# main.net
KiCad netlist of a schematic drawn in EAGLE
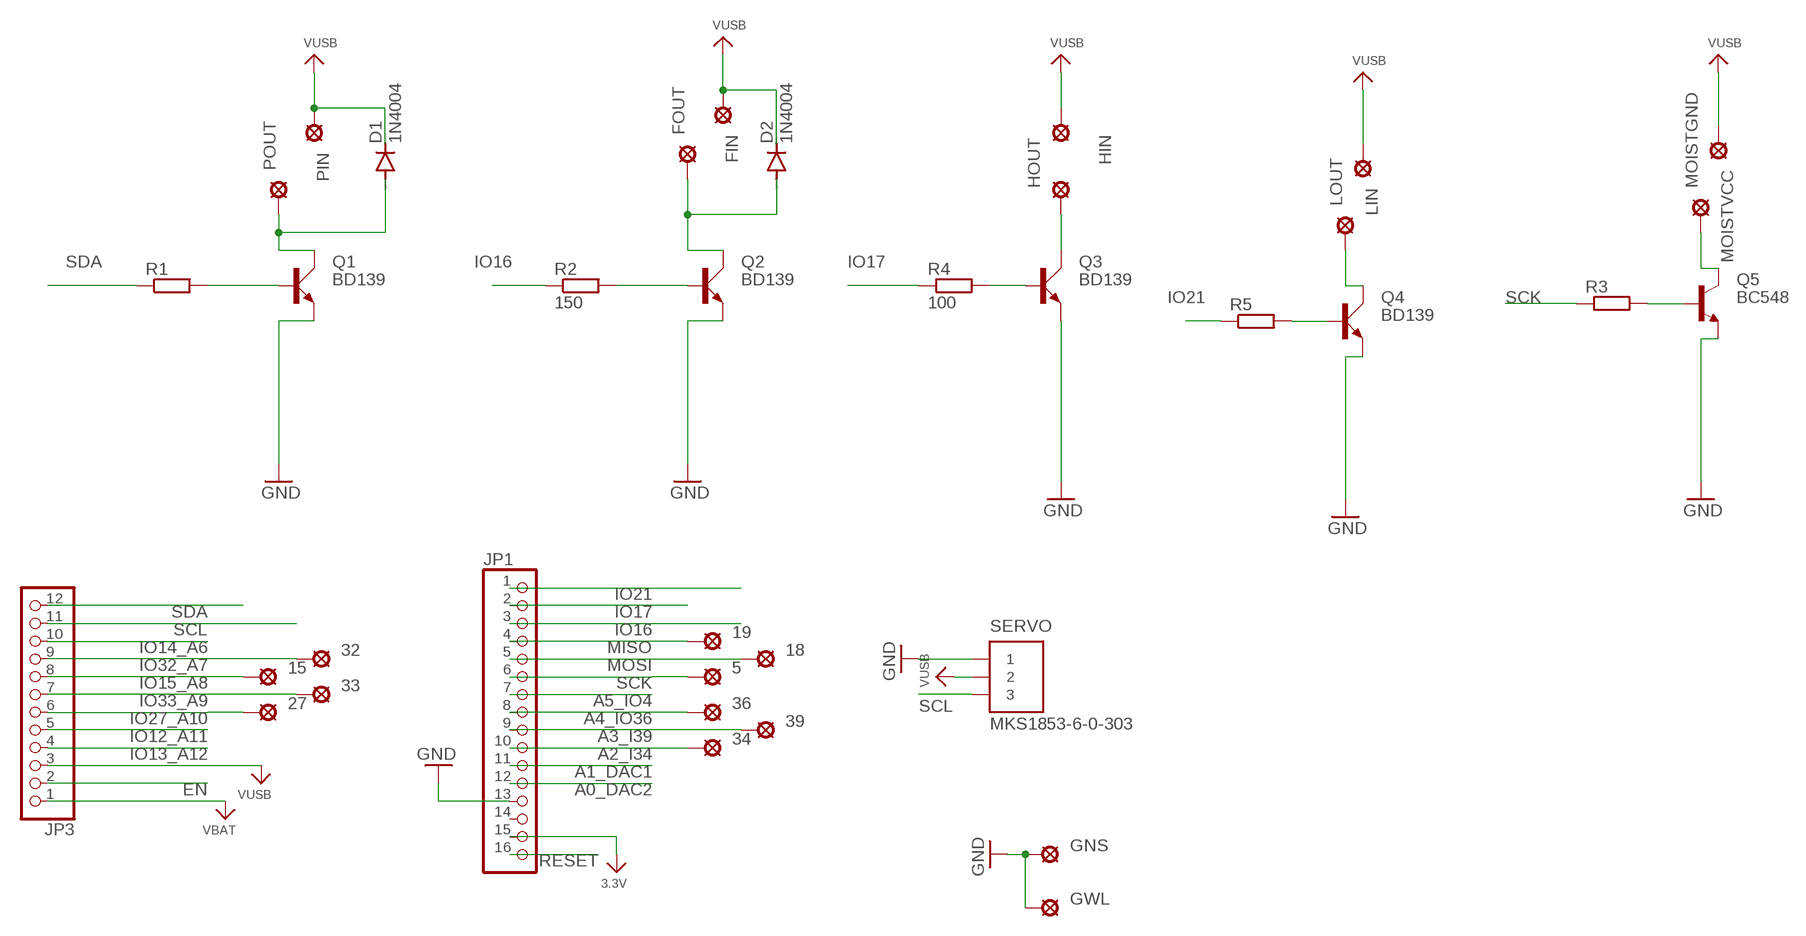
[diagram p0: schematic, sheet 1]

(export (version "E")
  (design (tool "Eeschema 10.0.6"))
  (components
    (comp (ref "5")
      (value "SE13")
      (footprint "eagle-import:SE13")
      (libsource (lib "eagle-import") (part "SE13"))
    )
    (comp (ref "15")
      (value "SE13")
      (footprint "eagle-import:SE13")
      (libsource (lib "eagle-import") (part "SE13"))
    )
    (comp (ref "18")
      (value "SE13")
      (footprint "eagle-import:SE13")
      (libsource (lib "eagle-import") (part "SE13"))
    )
    (comp (ref "19")
      (value "SE13")
      (footprint "eagle-import:SE13")
      (libsource (lib "eagle-import") (part "SE13"))
    )
    (comp (ref "27")
      (value "SE13")
      (footprint "eagle-import:SE13")
      (libsource (lib "eagle-import") (part "SE13"))
    )
    (comp (ref "32")
      (value "SE13")
      (footprint "eagle-import:SE13")
      (libsource (lib "eagle-import") (part "SE13"))
    )
    (comp (ref "33")
      (value "SE13")
      (footprint "eagle-import:SE13")
      (libsource (lib "eagle-import") (part "SE13"))
    )
    (comp (ref "34")
      (value "SE13")
      (footprint "eagle-import:SE13")
      (libsource (lib "eagle-import") (part "SE13"))
    )
    (comp (ref "36")
      (value "SE13")
      (footprint "eagle-import:SE13")
      (libsource (lib "eagle-import") (part "SE13"))
    )
    (comp (ref "39")
      (value "SE13")
      (footprint "eagle-import:SE13")
      (libsource (lib "eagle-import") (part "SE13"))
    )
    (comp (ref "D1")
      (value "1N4004")
      (footprint "eagle-import:DO41-10")
      (libsource (lib "eagle-import") (part "1N4004"))
    )
    (comp (ref "D2")
      (value "1N4004")
      (footprint "eagle-import:DO41-10")
      (libsource (lib "eagle-import") (part "1N4004"))
    )
    (comp (ref "FIN")
      (value "SE13")
      (footprint "eagle-import:SE13")
      (libsource (lib "eagle-import") (part "SE13"))
    )
    (comp (ref "FOUT")
      (value "SE13")
      (footprint "eagle-import:SE13")
      (libsource (lib "eagle-import") (part "SE13"))
    )
    (comp (ref "GNS")
      (value "SE13")
      (footprint "eagle-import:SE13")
      (libsource (lib "eagle-import") (part "SE13"))
    )
    (comp (ref "GWL")
      (value "SE13")
      (footprint "eagle-import:SE13")
      (libsource (lib "eagle-import") (part "SE13"))
    )
    (comp (ref "HIN")
      (value "SE13")
      (footprint "eagle-import:SE13")
      (libsource (lib "eagle-import") (part "SE13"))
    )
    (comp (ref "HOUT")
      (value "SE13")
      (footprint "eagle-import:SE13")
      (libsource (lib "eagle-import") (part "SE13"))
    )
    (comp (ref "JP1")
      (value "HEADER-1X16_MIN")
      (footprint "eagle-import:1X16_ROUND_MIN")
      (libsource (lib "eagle-import") (part "HEADER-1X16_MIN"))
    )
    (comp (ref "JP3")
      (value "HEADER-1X12_MIN")
      (footprint "eagle-import:1X12_ROUND_MIN")
      (libsource (lib "eagle-import") (part "HEADER-1X12_MIN"))
    )
    (comp (ref "LIN")
      (value "SE13")
      (footprint "eagle-import:SE13")
      (libsource (lib "eagle-import") (part "SE13"))
    )
    (comp (ref "LOUT")
      (value "SE13")
      (footprint "eagle-import:SE13")
      (libsource (lib "eagle-import") (part "SE13"))
    )
    (comp (ref "MOISTGND")
      (value "SE13")
      (footprint "eagle-import:SE13")
      (libsource (lib "eagle-import") (part "SE13"))
    )
    (comp (ref "MOISTVCC")
      (value "SE13")
      (footprint "eagle-import:SE13")
      (libsource (lib "eagle-import") (part "SE13"))
    )
    (comp (ref "PIN")
      (value "SE13")
      (footprint "eagle-import:SE13")
      (libsource (lib "eagle-import") (part "SE13"))
    )
    (comp (ref "POUT")
      (value "SE13")
      (footprint "eagle-import:SE13")
      (libsource (lib "eagle-import") (part "SE13"))
    )
    (comp (ref "Q1")
      (value "BD139")
      (footprint "eagle-import:TO126AV")
      (libsource (lib "eagle-import") (part "BD139"))
    )
    (comp (ref "Q2")
      (value "BD139")
      (footprint "eagle-import:TO126AV")
      (libsource (lib "eagle-import") (part "BD139"))
    )
    (comp (ref "Q3")
      (value "BD139")
      (footprint "eagle-import:TO126AV")
      (libsource (lib "eagle-import") (part "BD139"))
    )
    (comp (ref "Q4")
      (value "BD139")
      (footprint "eagle-import:TO126AV")
      (libsource (lib "eagle-import") (part "BD139"))
    )
    (comp (ref "Q5")
      (value "BC548")
      (footprint "eagle-import:TO92-EBC")
      (libsource (lib "eagle-import") (part "BC548"))
    )
    (comp (ref "R1")
      (value "R-EU_R0805")
      (footprint "eagle-import:R0805")
      (libsource (lib "eagle-import") (part "R-EU_R0805"))
    )
    (comp (ref "R2")
      (value "150")
      (footprint "eagle-import:R0805")
      (libsource (lib "eagle-import") (part "R-EU_R0805"))
    )
    (comp (ref "R3")
      (value "R-EU_R0805")
      (footprint "eagle-import:R0805")
      (libsource (lib "eagle-import") (part "R-EU_R0805"))
    )
    (comp (ref "R4")
      (value "100")
      (footprint "eagle-import:R0805")
      (libsource (lib "eagle-import") (part "R-EU_R0805"))
    )
    (comp (ref "R5")
      (value "R-EU_R0805")
      (footprint "eagle-import:R0805")
      (libsource (lib "eagle-import") (part "R-EU_R0805"))
    )
    (comp (ref "SERVO")
      (value "MKS1853-6-0-303")
      (footprint "eagle-import:MKS1853-6-0-303")
      (libsource (lib "eagle-import") (part "MKS1853-6-0-303"))
    )
  )
  (nets
    (net (code "1") (name "/A0_DAC2") (class "Default")
      (node (ref "JP1") (pin "12") (pinfunction "12_12") (pintype "passive"))
    )
    (net (code "2") (name "/A1_DAC1") (class "Default")
      (node (ref "JP1") (pin "11") (pinfunction "11_11") (pintype "passive"))
    )
    (net (code "3") (name "/A2_I34") (class "Default")
      (node (ref "34") (pin "MP") (pinfunction "MP_MP") (pintype "passive"))
      (node (ref "JP1") (pin "10") (pinfunction "10_10") (pintype "passive"))
    )
    (net (code "4") (name "/A3_I39") (class "Default")
      (node (ref "39") (pin "MP") (pinfunction "MP_MP") (pintype "passive"))
      (node (ref "JP1") (pin "9") (pinfunction "9_9") (pintype "passive"))
    )
    (net (code "5") (name "/A4_IO36") (class "Default")
      (node (ref "36") (pin "MP") (pinfunction "MP_MP") (pintype "passive"))
      (node (ref "JP1") (pin "8") (pinfunction "8_8") (pintype "passive"))
    )
    (net (code "6") (name "/A5_IO4") (class "Default")
      (node (ref "JP1") (pin "7") (pinfunction "7_7") (pintype "passive"))
    )
    (net (code "7") (name "/EN") (class "Default")
      (node (ref "JP3") (pin "2") (pinfunction "2_2") (pintype "passive"))
    )
    (net (code "8") (name "/IO12_A11") (class "Default")
      (node (ref "JP3") (pin "5") (pinfunction "5_5") (pintype "passive"))
    )
    (net (code "9") (name "/IO13_A12") (class "Default")
      (node (ref "JP3") (pin "4") (pinfunction "4_4") (pintype "passive"))
    )
    (net (code "10") (name "/IO14_A6") (class "Default")
      (node (ref "JP3") (pin "10") (pinfunction "10_10") (pintype "passive"))
    )
    (net (code "11") (name "/IO15_A8") (class "Default")
      (node (ref "15") (pin "MP") (pinfunction "MP_MP") (pintype "passive"))
      (node (ref "JP3") (pin "8") (pinfunction "8_8") (pintype "passive"))
    )
    (net (code "12") (name "/IO16") (class "Default")
      (node (ref "JP1") (pin "3") (pinfunction "3_3") (pintype "passive"))
      (node (ref "R2") (pin "1") (pinfunction "1_1") (pintype "passive"))
    )
    (net (code "13") (name "/IO17") (class "Default")
      (node (ref "JP1") (pin "2") (pinfunction "2_2") (pintype "passive"))
      (node (ref "R4") (pin "1") (pinfunction "1_1") (pintype "passive"))
    )
    (net (code "14") (name "/IO21") (class "Default")
      (node (ref "JP1") (pin "1") (pinfunction "1_1") (pintype "passive"))
      (node (ref "R5") (pin "1") (pinfunction "1_1") (pintype "passive"))
    )
    (net (code "15") (name "/IO27_A10") (class "Default")
      (node (ref "27") (pin "MP") (pinfunction "MP_MP") (pintype "passive"))
      (node (ref "JP3") (pin "6") (pinfunction "6_6") (pintype "passive"))
    )
    (net (code "16") (name "/IO32_A7") (class "Default")
      (node (ref "32") (pin "MP") (pinfunction "MP_MP") (pintype "passive"))
      (node (ref "JP3") (pin "9") (pinfunction "9_9") (pintype "passive"))
    )
    (net (code "17") (name "/IO33_A9") (class "Default")
      (node (ref "33") (pin "MP") (pinfunction "MP_MP") (pintype "passive"))
      (node (ref "JP3") (pin "7") (pinfunction "7_7") (pintype "passive"))
    )
    (net (code "18") (name "/MISO") (class "Default")
      (node (ref "19") (pin "MP") (pinfunction "MP_MP") (pintype "passive"))
      (node (ref "JP1") (pin "4") (pinfunction "4_4") (pintype "passive"))
    )
    (net (code "19") (name "/MOSI") (class "Default")
      (node (ref "18") (pin "MP") (pinfunction "MP_MP") (pintype "passive"))
      (node (ref "JP1") (pin "5") (pinfunction "5_5") (pintype "passive"))
    )
    (net (code "20") (name "/RESET") (class "Default")
      (node (ref "JP1") (pin "16") (pinfunction "16_16") (pintype "passive"))
    )
    (net (code "21") (name "/SCK") (class "Default")
      (node (ref "5") (pin "MP") (pinfunction "MP_MP") (pintype "passive"))
      (node (ref "JP1") (pin "6") (pinfunction "6_6") (pintype "passive"))
      (node (ref "R3") (pin "1") (pinfunction "1_1") (pintype "passive"))
    )
    (net (code "22") (name "/SCL") (class "Default")
      (node (ref "JP3") (pin "11") (pinfunction "11_11") (pintype "passive"))
      (node (ref "SERVO") (pin "3") (pinfunction "3_3") (pintype "input"))
    )
    (net (code "23") (name "/SDA") (class "Default")
      (node (ref "JP3") (pin "12") (pinfunction "12_12") (pintype "passive"))
      (node (ref "R1") (pin "1") (pinfunction "1_1") (pintype "passive"))
    )
    (net (code "24") (name "3.3V") (class "Default")
      (node (ref "JP1") (pin "15") (pinfunction "15_15") (pintype "passive"))
    )
    (net (code "25") (name "GND") (class "Default")
      (node (ref "GNS") (pin "MP") (pinfunction "MP_MP") (pintype "passive"))
      (node (ref "GWL") (pin "MP") (pinfunction "MP_MP") (pintype "passive"))
      (node (ref "JP1") (pin "13") (pinfunction "13_13") (pintype "passive"))
      (node (ref "Q1") (pin "E") (pinfunction "E_E") (pintype "passive"))
      (node (ref "Q2") (pin "E") (pinfunction "E_E") (pintype "passive"))
      (node (ref "Q3") (pin "E") (pinfunction "E_E") (pintype "passive"))
      (node (ref "Q4") (pin "E") (pinfunction "E_E") (pintype "passive"))
      (node (ref "Q5") (pin "E") (pinfunction "E_E") (pintype "passive"))
      (node (ref "SERVO") (pin "1") (pinfunction "1_1") (pintype "input"))
    )
    (net (code "26") (name "Net-(D1-PadA)") (class "Default")
      (node (ref "D1") (pin "A") (pinfunction "A_A") (pintype "passive"))
      (node (ref "POUT") (pin "MP") (pinfunction "MP_MP") (pintype "passive"))
      (node (ref "Q1") (pin "C") (pinfunction "C_C") (pintype "passive"))
    )
    (net (code "27") (name "Net-(D2-PadA)") (class "Default")
      (node (ref "D2") (pin "A") (pinfunction "A_A") (pintype "passive"))
      (node (ref "FOUT") (pin "MP") (pinfunction "MP_MP") (pintype "passive"))
      (node (ref "Q2") (pin "C") (pinfunction "C_C") (pintype "passive"))
    )
    (net (code "28") (name "Net-(HOUT-PadMP)") (class "Default")
      (node (ref "HOUT") (pin "MP") (pinfunction "MP_MP") (pintype "passive"))
      (node (ref "Q3") (pin "C") (pinfunction "C_C") (pintype "passive"))
    )
    (net (code "29") (name "Net-(LOUT-PadMP)") (class "Default")
      (node (ref "LOUT") (pin "MP") (pinfunction "MP_MP") (pintype "passive"))
      (node (ref "Q4") (pin "C") (pinfunction "C_C") (pintype "passive"))
    )
    (net (code "30") (name "Net-(MOISTGND-PadMP)") (class "Default")
      (node (ref "MOISTGND") (pin "MP") (pinfunction "MP_MP") (pintype "passive"))
      (node (ref "Q5") (pin "C") (pinfunction "C_C") (pintype "passive"))
    )
    (net (code "31") (name "Net-(Q1-PadB)") (class "Default")
      (node (ref "Q1") (pin "B") (pinfunction "B_B") (pintype "passive"))
      (node (ref "R1") (pin "2") (pinfunction "2_2") (pintype "passive"))
    )
    (net (code "32") (name "Net-(Q2-PadB)") (class "Default")
      (node (ref "Q2") (pin "B") (pinfunction "B_B") (pintype "passive"))
      (node (ref "R2") (pin "2") (pinfunction "2_2") (pintype "passive"))
    )
    (net (code "33") (name "Net-(Q3-PadB)") (class "Default")
      (node (ref "Q3") (pin "B") (pinfunction "B_B") (pintype "passive"))
      (node (ref "R4") (pin "2") (pinfunction "2_2") (pintype "passive"))
    )
    (net (code "34") (name "Net-(Q4-PadB)") (class "Default")
      (node (ref "Q4") (pin "B") (pinfunction "B_B") (pintype "passive"))
      (node (ref "R5") (pin "2") (pinfunction "2_2") (pintype "passive"))
    )
    (net (code "35") (name "Net-(Q5-PadB)") (class "Default")
      (node (ref "Q5") (pin "B") (pinfunction "B_B") (pintype "passive"))
      (node (ref "R3") (pin "2") (pinfunction "2_2") (pintype "passive"))
    )
    (net (code "36") (name "VBAT") (class "Default")
      (node (ref "JP3") (pin "1") (pinfunction "1_1") (pintype "passive"))
    )
    (net (code "37") (name "VUSB") (class "Default")
      (node (ref "D1") (pin "C") (pinfunction "C_C") (pintype "passive"))
      (node (ref "D2") (pin "C") (pinfunction "C_C") (pintype "passive"))
      (node (ref "FIN") (pin "MP") (pinfunction "MP_MP") (pintype "passive"))
      (node (ref "HIN") (pin "MP") (pinfunction "MP_MP") (pintype "passive"))
      (node (ref "JP3") (pin "3") (pinfunction "3_3") (pintype "passive"))
      (node (ref "LIN") (pin "MP") (pinfunction "MP_MP") (pintype "passive"))
      (node (ref "MOISTVCC") (pin "MP") (pinfunction "MP_MP") (pintype "passive"))
      (node (ref "PIN") (pin "MP") (pinfunction "MP_MP") (pintype "passive"))
      (node (ref "SERVO") (pin "2") (pinfunction "2_2") (pintype "input"))
    )
    (net (code "38") (name "unconnected-(JP1-Pad14)") (class "Default")
      (node (ref "JP1") (pin "14") (pinfunction "14_14") (pintype "passive"))
    )
  )
)
